# mega-shield2.net
KiCad netlist of a schematic drawn in EAGLE
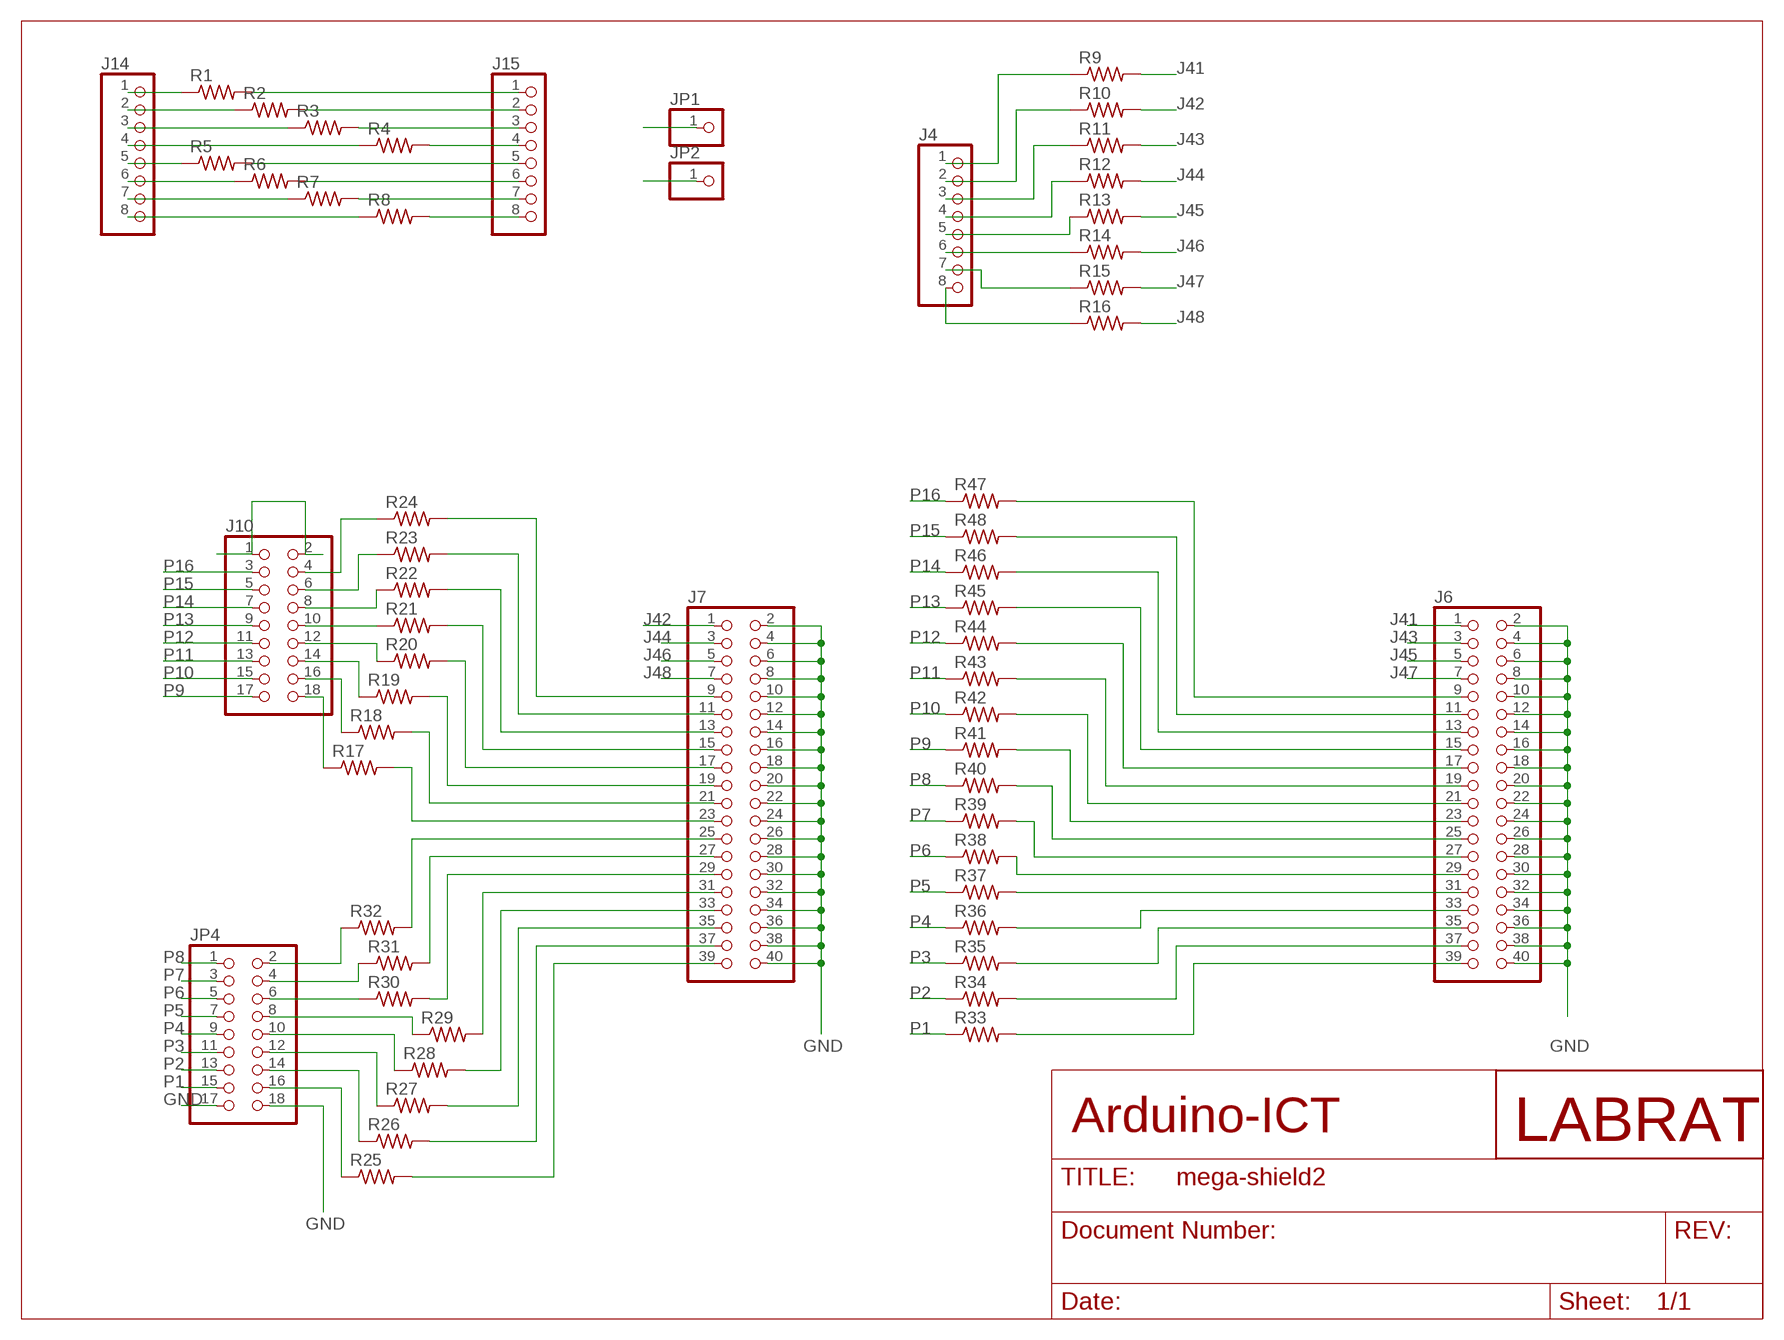
[diagram p0: schematic, sheet 1]

(export (version "E")
  (design (tool "Eeschema 10.0.6"))
  (components
    (comp (ref "J4")
      (value "PINHD-1X8BIG")
      (footprint "eagle-import:1X08-BIG")
      (libsource (lib "eagle-import") (part "PINHD-1X8BIG"))
    )
    (comp (ref "J6")
      (value "PINHD-2X20")
      (footprint "eagle-import:2X20")
      (libsource (lib "eagle-import") (part "PINHD-2X20"))
    )
    (comp (ref "J7")
      (value "PINHD-2X20")
      (footprint "eagle-import:2X20")
      (libsource (lib "eagle-import") (part "PINHD-2X20"))
    )
    (comp (ref "J10")
      (value "PINHD-2X9-BIG")
      (footprint "eagle-import:2X09-BIG")
      (libsource (lib "eagle-import") (part "PINHD-2X9-BIG"))
    )
    (comp (ref "J14")
      (value "PINHD-1X8BIG")
      (footprint "eagle-import:1X08-BIG")
      (libsource (lib "eagle-import") (part "PINHD-1X8BIG"))
    )
    (comp (ref "J15")
      (value "PINHD-1X8BIG")
      (footprint "eagle-import:1X08-BIG")
      (libsource (lib "eagle-import") (part "PINHD-1X8BIG"))
    )
    (comp (ref "JP1")
      (value "PINHD-1X1")
      (footprint "eagle-import:1X01")
      (libsource (lib "eagle-import") (part "PINHD-1X1"))
    )
    (comp (ref "JP2")
      (value "PINHD-1X1")
      (footprint "eagle-import:1X01")
      (libsource (lib "eagle-import") (part "PINHD-1X1"))
    )
    (comp (ref "JP4")
      (value "PINHD-2X9-BIG")
      (footprint "eagle-import:2X09-BIG")
      (libsource (lib "eagle-import") (part "PINHD-2X9-BIG"))
    )
    (comp (ref "R1")
      (value "R-US_0204/5")
      (footprint "eagle-import:0204_5")
      (libsource (lib "eagle-import") (part "R-US_0204/5"))
    )
    (comp (ref "R2")
      (value "R-US_0204/5")
      (footprint "eagle-import:0204_5")
      (libsource (lib "eagle-import") (part "R-US_0204/5"))
    )
    (comp (ref "R3")
      (value "R-US_0204/5")
      (footprint "eagle-import:0204_5")
      (libsource (lib "eagle-import") (part "R-US_0204/5"))
    )
    (comp (ref "R4")
      (value "R-US_0204/5")
      (footprint "eagle-import:0204_5")
      (libsource (lib "eagle-import") (part "R-US_0204/5"))
    )
    (comp (ref "R5")
      (value "R-US_0204/5")
      (footprint "eagle-import:0204_5")
      (libsource (lib "eagle-import") (part "R-US_0204/5"))
    )
    (comp (ref "R6")
      (value "R-US_0204/5")
      (footprint "eagle-import:0204_5")
      (libsource (lib "eagle-import") (part "R-US_0204/5"))
    )
    (comp (ref "R7")
      (value "R-US_0204/5")
      (footprint "eagle-import:0204_5")
      (libsource (lib "eagle-import") (part "R-US_0204/5"))
    )
    (comp (ref "R8")
      (value "R-US_0204/5")
      (footprint "eagle-import:0204_5")
      (libsource (lib "eagle-import") (part "R-US_0204/5"))
    )
    (comp (ref "R9")
      (value "R-US_0204/5")
      (footprint "eagle-import:0204_5")
      (libsource (lib "eagle-import") (part "R-US_0204/5"))
    )
    (comp (ref "R10")
      (value "R-US_0204/5")
      (footprint "eagle-import:0204_5")
      (libsource (lib "eagle-import") (part "R-US_0204/5"))
    )
    (comp (ref "R11")
      (value "R-US_0204/5")
      (footprint "eagle-import:0204_5")
      (libsource (lib "eagle-import") (part "R-US_0204/5"))
    )
    (comp (ref "R12")
      (value "R-US_0204/5")
      (footprint "eagle-import:0204_5")
      (libsource (lib "eagle-import") (part "R-US_0204/5"))
    )
    (comp (ref "R13")
      (value "R-US_0204/5")
      (footprint "eagle-import:0204_5")
      (libsource (lib "eagle-import") (part "R-US_0204/5"))
    )
    (comp (ref "R14")
      (value "R-US_0204/5")
      (footprint "eagle-import:0204_5")
      (libsource (lib "eagle-import") (part "R-US_0204/5"))
    )
    (comp (ref "R15")
      (value "R-US_0204/5")
      (footprint "eagle-import:0204_5")
      (libsource (lib "eagle-import") (part "R-US_0204/5"))
    )
    (comp (ref "R16")
      (value "R-US_0204/5")
      (footprint "eagle-import:0204_5")
      (libsource (lib "eagle-import") (part "R-US_0204/5"))
    )
    (comp (ref "R17")
      (value "R-US_0204/5")
      (footprint "eagle-import:0204_5")
      (libsource (lib "eagle-import") (part "R-US_0204/5"))
    )
    (comp (ref "R18")
      (value "R-US_0204/5")
      (footprint "eagle-import:0204_5")
      (libsource (lib "eagle-import") (part "R-US_0204/5"))
    )
    (comp (ref "R19")
      (value "R-US_0204/5")
      (footprint "eagle-import:0204_5")
      (libsource (lib "eagle-import") (part "R-US_0204/5"))
    )
    (comp (ref "R20")
      (value "R-US_0204/5")
      (footprint "eagle-import:0204_5")
      (libsource (lib "eagle-import") (part "R-US_0204/5"))
    )
    (comp (ref "R21")
      (value "R-US_0204/5")
      (footprint "eagle-import:0204_5")
      (libsource (lib "eagle-import") (part "R-US_0204/5"))
    )
    (comp (ref "R22")
      (value "R-US_0204/5")
      (footprint "eagle-import:0204_5")
      (libsource (lib "eagle-import") (part "R-US_0204/5"))
    )
    (comp (ref "R23")
      (value "R-US_0204/5")
      (footprint "eagle-import:0204_5")
      (libsource (lib "eagle-import") (part "R-US_0204/5"))
    )
    (comp (ref "R24")
      (value "R-US_0204/5")
      (footprint "eagle-import:0204_5")
      (libsource (lib "eagle-import") (part "R-US_0204/5"))
    )
    (comp (ref "R25")
      (value "R-US_0204/5")
      (footprint "eagle-import:0204_5")
      (libsource (lib "eagle-import") (part "R-US_0204/5"))
    )
    (comp (ref "R26")
      (value "R-US_0204/5")
      (footprint "eagle-import:0204_5")
      (libsource (lib "eagle-import") (part "R-US_0204/5"))
    )
    (comp (ref "R27")
      (value "R-US_0204/5")
      (footprint "eagle-import:0204_5")
      (libsource (lib "eagle-import") (part "R-US_0204/5"))
    )
    (comp (ref "R28")
      (value "R-US_0204/5")
      (footprint "eagle-import:0204_5")
      (libsource (lib "eagle-import") (part "R-US_0204/5"))
    )
    (comp (ref "R29")
      (value "R-US_0204/5")
      (footprint "eagle-import:0204_5")
      (libsource (lib "eagle-import") (part "R-US_0204/5"))
    )
    (comp (ref "R30")
      (value "R-US_0204/5")
      (footprint "eagle-import:0204_5")
      (libsource (lib "eagle-import") (part "R-US_0204/5"))
    )
    (comp (ref "R31")
      (value "R-US_0204/5")
      (footprint "eagle-import:0204_5")
      (libsource (lib "eagle-import") (part "R-US_0204/5"))
    )
    (comp (ref "R32")
      (value "R-US_0204/5")
      (footprint "eagle-import:0204_5")
      (libsource (lib "eagle-import") (part "R-US_0204/5"))
    )
    (comp (ref "R33")
      (value "R-US_0204/5")
      (footprint "eagle-import:0204_5")
      (libsource (lib "eagle-import") (part "R-US_0204/5"))
    )
    (comp (ref "R34")
      (value "R-US_0204/5")
      (footprint "eagle-import:0204_5")
      (libsource (lib "eagle-import") (part "R-US_0204/5"))
    )
    (comp (ref "R35")
      (value "R-US_0204/5")
      (footprint "eagle-import:0204_5")
      (libsource (lib "eagle-import") (part "R-US_0204/5"))
    )
    (comp (ref "R36")
      (value "R-US_0204/5")
      (footprint "eagle-import:0204_5")
      (libsource (lib "eagle-import") (part "R-US_0204/5"))
    )
    (comp (ref "R37")
      (value "R-US_0204/5")
      (footprint "eagle-import:0204_5")
      (libsource (lib "eagle-import") (part "R-US_0204/5"))
    )
    (comp (ref "R38")
      (value "R-US_0204/5")
      (footprint "eagle-import:0204_5")
      (libsource (lib "eagle-import") (part "R-US_0204/5"))
    )
    (comp (ref "R39")
      (value "R-US_0204/5")
      (footprint "eagle-import:0204_5")
      (libsource (lib "eagle-import") (part "R-US_0204/5"))
    )
    (comp (ref "R40")
      (value "R-US_0204/5")
      (footprint "eagle-import:0204_5")
      (libsource (lib "eagle-import") (part "R-US_0204/5"))
    )
    (comp (ref "R41")
      (value "R-US_0204/5")
      (footprint "eagle-import:0204_5")
      (libsource (lib "eagle-import") (part "R-US_0204/5"))
    )
    (comp (ref "R42")
      (value "R-US_0204/5")
      (footprint "eagle-import:0204_5")
      (libsource (lib "eagle-import") (part "R-US_0204/5"))
    )
    (comp (ref "R43")
      (value "R-US_0204/5")
      (footprint "eagle-import:0204_5")
      (libsource (lib "eagle-import") (part "R-US_0204/5"))
    )
    (comp (ref "R44")
      (value "R-US_0204/5")
      (footprint "eagle-import:0204_5")
      (libsource (lib "eagle-import") (part "R-US_0204/5"))
    )
    (comp (ref "R45")
      (value "R-US_0204/5")
      (footprint "eagle-import:0204_5")
      (libsource (lib "eagle-import") (part "R-US_0204/5"))
    )
    (comp (ref "R46")
      (value "R-US_0204/5")
      (footprint "eagle-import:0204_5")
      (libsource (lib "eagle-import") (part "R-US_0204/5"))
    )
    (comp (ref "R47")
      (value "R-US_0204/5")
      (footprint "eagle-import:0204_5")
      (libsource (lib "eagle-import") (part "R-US_0204/5"))
    )
    (comp (ref "R48")
      (value "R-US_0204/5")
      (footprint "eagle-import:0204_5")
      (libsource (lib "eagle-import") (part "R-US_0204/5"))
    )
    (comp (ref "U$1")
      (value "LOGOLABRAT")
      (footprint "eagle-import:LOGO")
      (libsource (lib "eagle-import") (part "LOGOLABRAT"))
    )
  )
  (nets
    (net (code "1") (name "/GND") (class "Default")
      (node (ref "J6") (pin "10") (pinfunction "10_10") (pintype "passive"))
      (node (ref "J6") (pin "12") (pinfunction "12_12") (pintype "passive"))
      (node (ref "J6") (pin "14") (pinfunction "14_14") (pintype "passive"))
      (node (ref "J6") (pin "16") (pinfunction "16_16") (pintype "passive"))
      (node (ref "J6") (pin "18") (pinfunction "18_18") (pintype "passive"))
      (node (ref "J6") (pin "2") (pinfunction "2_2") (pintype "passive"))
      (node (ref "J6") (pin "20") (pinfunction "20_20") (pintype "passive"))
      (node (ref "J6") (pin "22") (pinfunction "22_22") (pintype "passive"))
      (node (ref "J6") (pin "24") (pinfunction "24_24") (pintype "passive"))
      (node (ref "J6") (pin "26") (pinfunction "26_26") (pintype "passive"))
      (node (ref "J6") (pin "28") (pinfunction "28_28") (pintype "passive"))
      (node (ref "J6") (pin "30") (pinfunction "30_30") (pintype "passive"))
      (node (ref "J6") (pin "32") (pinfunction "32_32") (pintype "passive"))
      (node (ref "J6") (pin "34") (pinfunction "34_34") (pintype "passive"))
      (node (ref "J6") (pin "36") (pinfunction "36_36") (pintype "passive"))
      (node (ref "J6") (pin "38") (pinfunction "38_38") (pintype "passive"))
      (node (ref "J6") (pin "4") (pinfunction "4_4") (pintype "passive"))
      (node (ref "J6") (pin "40") (pinfunction "40_40") (pintype "passive"))
      (node (ref "J6") (pin "6") (pinfunction "6_6") (pintype "passive"))
      (node (ref "J6") (pin "8") (pinfunction "8_8") (pintype "passive"))
      (node (ref "J7") (pin "10") (pinfunction "10_10") (pintype "passive"))
      (node (ref "J7") (pin "12") (pinfunction "12_12") (pintype "passive"))
      (node (ref "J7") (pin "14") (pinfunction "14_14") (pintype "passive"))
      (node (ref "J7") (pin "16") (pinfunction "16_16") (pintype "passive"))
      (node (ref "J7") (pin "18") (pinfunction "18_18") (pintype "passive"))
      (node (ref "J7") (pin "2") (pinfunction "2_2") (pintype "passive"))
      (node (ref "J7") (pin "20") (pinfunction "20_20") (pintype "passive"))
      (node (ref "J7") (pin "22") (pinfunction "22_22") (pintype "passive"))
      (node (ref "J7") (pin "24") (pinfunction "24_24") (pintype "passive"))
      (node (ref "J7") (pin "26") (pinfunction "26_26") (pintype "passive"))
      (node (ref "J7") (pin "28") (pinfunction "28_28") (pintype "passive"))
      (node (ref "J7") (pin "30") (pinfunction "30_30") (pintype "passive"))
      (node (ref "J7") (pin "32") (pinfunction "32_32") (pintype "passive"))
      (node (ref "J7") (pin "34") (pinfunction "34_34") (pintype "passive"))
      (node (ref "J7") (pin "36") (pinfunction "36_36") (pintype "passive"))
      (node (ref "J7") (pin "38") (pinfunction "38_38") (pintype "passive"))
      (node (ref "J7") (pin "4") (pinfunction "4_4") (pintype "passive"))
      (node (ref "J7") (pin "40") (pinfunction "40_40") (pintype "passive"))
      (node (ref "J7") (pin "6") (pinfunction "6_6") (pintype "passive"))
      (node (ref "J7") (pin "8") (pinfunction "8_8") (pintype "passive"))
      (node (ref "JP1") (pin "1") (pinfunction "1_1") (pintype "passive"))
      (node (ref "JP2") (pin "1") (pinfunction "1_1") (pintype "passive"))
      (node (ref "JP4") (pin "17") (pinfunction "17_17") (pintype "passive"))
      (node (ref "JP4") (pin "18") (pinfunction "18_18") (pintype "passive"))
    )
    (net (code "2") (name "/J41") (class "Default")
      (node (ref "J6") (pin "1") (pinfunction "1_1") (pintype "passive"))
      (node (ref "R9") (pin "2") (pinfunction "2_2") (pintype "passive"))
    )
    (net (code "3") (name "/J42") (class "Default")
      (node (ref "J7") (pin "1") (pinfunction "1_1") (pintype "passive"))
      (node (ref "R10") (pin "2") (pinfunction "2_2") (pintype "passive"))
    )
    (net (code "4") (name "/J43") (class "Default")
      (node (ref "J6") (pin "3") (pinfunction "3_3") (pintype "passive"))
      (node (ref "R11") (pin "2") (pinfunction "2_2") (pintype "passive"))
    )
    (net (code "5") (name "/J44") (class "Default")
      (node (ref "J7") (pin "3") (pinfunction "3_3") (pintype "passive"))
      (node (ref "R12") (pin "2") (pinfunction "2_2") (pintype "passive"))
    )
    (net (code "6") (name "/J45") (class "Default")
      (node (ref "J6") (pin "5") (pinfunction "5_5") (pintype "passive"))
      (node (ref "R13") (pin "2") (pinfunction "2_2") (pintype "passive"))
    )
    (net (code "7") (name "/J46") (class "Default")
      (node (ref "J7") (pin "5") (pinfunction "5_5") (pintype "passive"))
      (node (ref "R14") (pin "2") (pinfunction "2_2") (pintype "passive"))
    )
    (net (code "8") (name "/J47") (class "Default")
      (node (ref "J6") (pin "7") (pinfunction "7_7") (pintype "passive"))
      (node (ref "R15") (pin "2") (pinfunction "2_2") (pintype "passive"))
    )
    (net (code "9") (name "/J48") (class "Default")
      (node (ref "J7") (pin "7") (pinfunction "7_7") (pintype "passive"))
      (node (ref "R16") (pin "2") (pinfunction "2_2") (pintype "passive"))
    )
    (net (code "10") (name "/P1") (class "Default")
      (node (ref "JP4") (pin "15") (pinfunction "15_15") (pintype "passive"))
      (node (ref "R33") (pin "1") (pinfunction "1_1") (pintype "passive"))
    )
    (net (code "11") (name "/P2") (class "Default")
      (node (ref "JP4") (pin "13") (pinfunction "13_13") (pintype "passive"))
      (node (ref "R34") (pin "1") (pinfunction "1_1") (pintype "passive"))
    )
    (net (code "12") (name "/P3") (class "Default")
      (node (ref "JP4") (pin "11") (pinfunction "11_11") (pintype "passive"))
      (node (ref "R35") (pin "1") (pinfunction "1_1") (pintype "passive"))
    )
    (net (code "13") (name "/P4") (class "Default")
      (node (ref "JP4") (pin "9") (pinfunction "9_9") (pintype "passive"))
      (node (ref "R36") (pin "1") (pinfunction "1_1") (pintype "passive"))
    )
    (net (code "14") (name "/P5") (class "Default")
      (node (ref "JP4") (pin "7") (pinfunction "7_7") (pintype "passive"))
      (node (ref "R37") (pin "1") (pinfunction "1_1") (pintype "passive"))
    )
    (net (code "15") (name "/P6") (class "Default")
      (node (ref "JP4") (pin "5") (pinfunction "5_5") (pintype "passive"))
      (node (ref "R38") (pin "1") (pinfunction "1_1") (pintype "passive"))
    )
    (net (code "16") (name "/P7") (class "Default")
      (node (ref "JP4") (pin "3") (pinfunction "3_3") (pintype "passive"))
      (node (ref "R39") (pin "1") (pinfunction "1_1") (pintype "passive"))
    )
    (net (code "17") (name "/P8") (class "Default")
      (node (ref "JP4") (pin "1") (pinfunction "1_1") (pintype "passive"))
      (node (ref "R40") (pin "1") (pinfunction "1_1") (pintype "passive"))
    )
    (net (code "18") (name "/P9") (class "Default")
      (node (ref "J10") (pin "17") (pinfunction "17_17") (pintype "passive"))
      (node (ref "R41") (pin "1") (pinfunction "1_1") (pintype "passive"))
    )
    (net (code "19") (name "/P10") (class "Default")
      (node (ref "J10") (pin "15") (pinfunction "15_15") (pintype "passive"))
      (node (ref "R42") (pin "1") (pinfunction "1_1") (pintype "passive"))
    )
    (net (code "20") (name "/P11") (class "Default")
      (node (ref "J10") (pin "13") (pinfunction "13_13") (pintype "passive"))
      (node (ref "R43") (pin "1") (pinfunction "1_1") (pintype "passive"))
    )
    (net (code "21") (name "/P12") (class "Default")
      (node (ref "J10") (pin "11") (pinfunction "11_11") (pintype "passive"))
      (node (ref "R44") (pin "1") (pinfunction "1_1") (pintype "passive"))
    )
    (net (code "22") (name "/P13") (class "Default")
      (node (ref "J10") (pin "9") (pinfunction "9_9") (pintype "passive"))
      (node (ref "R45") (pin "1") (pinfunction "1_1") (pintype "passive"))
    )
    (net (code "23") (name "/P14") (class "Default")
      (node (ref "J10") (pin "7") (pinfunction "7_7") (pintype "passive"))
      (node (ref "R46") (pin "1") (pinfunction "1_1") (pintype "passive"))
    )
    (net (code "24") (name "/P15") (class "Default")
      (node (ref "J10") (pin "5") (pinfunction "5_5") (pintype "passive"))
      (node (ref "R48") (pin "1") (pinfunction "1_1") (pintype "passive"))
    )
    (net (code "25") (name "/P16") (class "Default")
      (node (ref "J10") (pin "3") (pinfunction "3_3") (pintype "passive"))
      (node (ref "R47") (pin "1") (pinfunction "1_1") (pintype "passive"))
    )
    (net (code "26") (name "Net-(J4-Pad1)") (class "Default")
      (node (ref "J4") (pin "1") (pinfunction "1_1") (pintype "passive"))
      (node (ref "R9") (pin "1") (pinfunction "1_1") (pintype "passive"))
    )
    (net (code "27") (name "Net-(J4-Pad2)") (class "Default")
      (node (ref "J4") (pin "2") (pinfunction "2_2") (pintype "passive"))
      (node (ref "R10") (pin "1") (pinfunction "1_1") (pintype "passive"))
    )
    (net (code "28") (name "Net-(J4-Pad3)") (class "Default")
      (node (ref "J4") (pin "3") (pinfunction "3_3") (pintype "passive"))
      (node (ref "R11") (pin "1") (pinfunction "1_1") (pintype "passive"))
    )
    (net (code "29") (name "Net-(J4-Pad4)") (class "Default")
      (node (ref "J4") (pin "4") (pinfunction "4_4") (pintype "passive"))
      (node (ref "R12") (pin "1") (pinfunction "1_1") (pintype "passive"))
    )
    (net (code "30") (name "Net-(J4-Pad5)") (class "Default")
      (node (ref "J4") (pin "5") (pinfunction "5_5") (pintype "passive"))
      (node (ref "R13") (pin "1") (pinfunction "1_1") (pintype "passive"))
    )
    (net (code "31") (name "Net-(J4-Pad6)") (class "Default")
      (node (ref "J4") (pin "6") (pinfunction "6_6") (pintype "passive"))
      (node (ref "R14") (pin "1") (pinfunction "1_1") (pintype "passive"))
    )
    (net (code "32") (name "Net-(J4-Pad7)") (class "Default")
      (node (ref "J4") (pin "7") (pinfunction "7_7") (pintype "passive"))
      (node (ref "R15") (pin "1") (pinfunction "1_1") (pintype "passive"))
    )
    (net (code "33") (name "Net-(J4-Pad8)") (class "Default")
      (node (ref "J4") (pin "8") (pinfunction "8_8") (pintype "passive"))
      (node (ref "R16") (pin "1") (pinfunction "1_1") (pintype "passive"))
    )
    (net (code "34") (name "Net-(J6-Pad9)") (class "Default")
      (node (ref "J6") (pin "9") (pinfunction "9_9") (pintype "passive"))
      (node (ref "R47") (pin "2") (pinfunction "2_2") (pintype "passive"))
    )
    (net (code "35") (name "Net-(J6-Pad11)") (class "Default")
      (node (ref "J6") (pin "11") (pinfunction "11_11") (pintype "passive"))
      (node (ref "R48") (pin "2") (pinfunction "2_2") (pintype "passive"))
    )
    (net (code "36") (name "Net-(J6-Pad13)") (class "Default")
      (node (ref "J6") (pin "13") (pinfunction "13_13") (pintype "passive"))
      (node (ref "R46") (pin "2") (pinfunction "2_2") (pintype "passive"))
    )
    (net (code "37") (name "Net-(J6-Pad15)") (class "Default")
      (node (ref "J6") (pin "15") (pinfunction "15_15") (pintype "passive"))
      (node (ref "R45") (pin "2") (pinfunction "2_2") (pintype "passive"))
    )
    (net (code "38") (name "Net-(J6-Pad17)") (class "Default")
      (node (ref "J6") (pin "17") (pinfunction "17_17") (pintype "passive"))
      (node (ref "R44") (pin "2") (pinfunction "2_2") (pintype "passive"))
    )
    (net (code "39") (name "Net-(J6-Pad19)") (class "Default")
      (node (ref "J6") (pin "19") (pinfunction "19_19") (pintype "passive"))
      (node (ref "R43") (pin "2") (pinfunction "2_2") (pintype "passive"))
    )
    (net (code "40") (name "Net-(J6-Pad21)") (class "Default")
      (node (ref "J6") (pin "21") (pinfunction "21_21") (pintype "passive"))
      (node (ref "R42") (pin "2") (pinfunction "2_2") (pintype "passive"))
    )
    (net (code "41") (name "Net-(J6-Pad23)") (class "Default")
      (node (ref "J6") (pin "23") (pinfunction "23_23") (pintype "passive"))
      (node (ref "R41") (pin "2") (pinfunction "2_2") (pintype "passive"))
    )
    (net (code "42") (name "Net-(J6-Pad25)") (class "Default")
      (node (ref "J6") (pin "25") (pinfunction "25_25") (pintype "passive"))
      (node (ref "R40") (pin "2") (pinfunction "2_2") (pintype "passive"))
    )
    (net (code "43") (name "Net-(J6-Pad27)") (class "Default")
      (node (ref "J6") (pin "27") (pinfunction "27_27") (pintype "passive"))
      (node (ref "R39") (pin "2") (pinfunction "2_2") (pintype "passive"))
    )
    (net (code "44") (name "Net-(J6-Pad29)") (class "Default")
      (node (ref "J6") (pin "29") (pinfunction "29_29") (pintype "passive"))
      (node (ref "R38") (pin "2") (pinfunction "2_2") (pintype "passive"))
    )
    (net (code "45") (name "Net-(J6-Pad31)") (class "Default")
      (node (ref "J6") (pin "31") (pinfunction "31_31") (pintype "passive"))
      (node (ref "R37") (pin "2") (pinfunction "2_2") (pintype "passive"))
    )
    (net (code "46") (name "Net-(J6-Pad33)") (class "Default")
      (node (ref "J6") (pin "33") (pinfunction "33_33") (pintype "passive"))
      (node (ref "R36") (pin "2") (pinfunction "2_2") (pintype "passive"))
    )
    (net (code "47") (name "Net-(J6-Pad35)") (class "Default")
      (node (ref "J6") (pin "35") (pinfunction "35_35") (pintype "passive"))
      (node (ref "R35") (pin "2") (pinfunction "2_2") (pintype "passive"))
    )
    (net (code "48") (name "Net-(J6-Pad37)") (class "Default")
      (node (ref "J6") (pin "37") (pinfunction "37_37") (pintype "passive"))
      (node (ref "R34") (pin "2") (pinfunction "2_2") (pintype "passive"))
    )
    (net (code "49") (name "Net-(J6-Pad39)") (class "Default")
      (node (ref "J6") (pin "39") (pinfunction "39_39") (pintype "passive"))
      (node (ref "R33") (pin "2") (pinfunction "2_2") (pintype "passive"))
    )
    (net (code "50") (name "Net-(J7-Pad9)") (class "Default")
      (node (ref "J7") (pin "9") (pinfunction "9_9") (pintype "passive"))
      (node (ref "R24") (pin "2") (pinfunction "2_2") (pintype "passive"))
    )
    (net (code "51") (name "Net-(J7-Pad11)") (class "Default")
      (node (ref "J7") (pin "11") (pinfunction "11_11") (pintype "passive"))
      (node (ref "R23") (pin "2") (pinfunction "2_2") (pintype "passive"))
    )
    (net (code "52") (name "Net-(J7-Pad13)") (class "Default")
      (node (ref "J7") (pin "13") (pinfunction "13_13") (pintype "passive"))
      (node (ref "R22") (pin "2") (pinfunction "2_2") (pintype "passive"))
    )
    (net (code "53") (name "Net-(J7-Pad15)") (class "Default")
      (node (ref "J7") (pin "15") (pinfunction "15_15") (pintype "passive"))
      (node (ref "R21") (pin "2") (pinfunction "2_2") (pintype "passive"))
    )
    (net (code "54") (name "Net-(J7-Pad17)") (class "Default")
      (node (ref "J7") (pin "17") (pinfunction "17_17") (pintype "passive"))
      (node (ref "R20") (pin "2") (pinfunction "2_2") (pintype "passive"))
    )
    (net (code "55") (name "Net-(J7-Pad19)") (class "Default")
      (node (ref "J7") (pin "19") (pinfunction "19_19") (pintype "passive"))
      (node (ref "R19") (pin "2") (pinfunction "2_2") (pintype "passive"))
    )
    (net (code "56") (name "Net-(J7-Pad21)") (class "Default")
      (node (ref "J7") (pin "21") (pinfunction "21_21") (pintype "passive"))
      (node (ref "R18") (pin "2") (pinfunction "2_2") (pintype "passive"))
    )
    (net (code "57") (name "Net-(J7-Pad23)") (class "Default")
      (node (ref "J7") (pin "23") (pinfunction "23_23") (pintype "passive"))
      (node (ref "R17") (pin "2") (pinfunction "2_2") (pintype "passive"))
    )
    (net (code "58") (name "Net-(J7-Pad25)") (class "Default")
      (node (ref "J7") (pin "25") (pinfunction "25_25") (pintype "passive"))
      (node (ref "R32") (pin "2") (pinfunction "2_2") (pintype "passive"))
    )
    (net (code "59") (name "Net-(J7-Pad27)") (class "Default")
      (node (ref "J7") (pin "27") (pinfunction "27_27") (pintype "passive"))
      (node (ref "R31") (pin "2") (pinfunction "2_2") (pintype "passive"))
    )
    (net (code "60") (name "Net-(J7-Pad29)") (class "Default")
      (node (ref "J7") (pin "29") (pinfunction "29_29") (pintype "passive"))
      (node (ref "R30") (pin "2") (pinfunction "2_2") (pintype "passive"))
    )
    (net (code "61") (name "Net-(J7-Pad31)") (class "Default")
      (node (ref "J7") (pin "31") (pinfunction "31_31") (pintype "passive"))
      (node (ref "R29") (pin "2") (pinfunction "2_2") (pintype "passive"))
    )
    (net (code "62") (name "Net-(J7-Pad33)") (class "Default")
      (node (ref "J7") (pin "33") (pinfunction "33_33") (pintype "passive"))
      (node (ref "R28") (pin "2") (pinfunction "2_2") (pintype "passive"))
    )
    (net (code "63") (name "Net-(J7-Pad35)") (class "Default")
      (node (ref "J7") (pin "35") (pinfunction "35_35") (pintype "passive"))
      (node (ref "R27") (pin "2") (pinfunction "2_2") (pintype "passive"))
    )
    (net (code "64") (name "Net-(J7-Pad37)") (class "Default")
      (node (ref "J7") (pin "37") (pinfunction "37_37") (pintype "passive"))
      (node (ref "R26") (pin "2") (pinfunction "2_2") (pintype "passive"))
    )
    (net (code "65") (name "Net-(J7-Pad39)") (class "Default")
      (node (ref "J7") (pin "39") (pinfunction "39_39") (pintype "passive"))
      (node (ref "R25") (pin "2") (pinfunction "2_2") (pintype "passive"))
    )
    (net (code "66") (name "Net-(J10-Pad1)") (class "Default")
      (node (ref "J10") (pin "1") (pinfunction "1_1") (pintype "passive"))
      (node (ref "J10") (pin "2") (pinfunction "2_2") (pintype "passive"))
    )
    (net (code "67") (name "Net-(J10-Pad4)") (class "Default")
      (node (ref "J10") (pin "4") (pinfunction "4_4") (pintype "passive"))
      (node (ref "R24") (pin "1") (pinfunction "1_1") (pintype "passive"))
    )
    (net (code "68") (name "Net-(J10-Pad6)") (class "Default")
      (node (ref "J10") (pin "6") (pinfunction "6_6") (pintype "passive"))
      (node (ref "R23") (pin "1") (pinfunction "1_1") (pintype "passive"))
    )
    (net (code "69") (name "Net-(J10-Pad8)") (class "Default")
      (node (ref "J10") (pin "8") (pinfunction "8_8") (pintype "passive"))
      (node (ref "R22") (pin "1") (pinfunction "1_1") (pintype "passive"))
    )
    (net (code "70") (name "Net-(J10-Pad10)") (class "Default")
      (node (ref "J10") (pin "10") (pinfunction "10_10") (pintype "passive"))
      (node (ref "R21") (pin "1") (pinfunction "1_1") (pintype "passive"))
    )
    (net (code "71") (name "Net-(J10-Pad12)") (class "Default")
      (node (ref "J10") (pin "12") (pinfunction "12_12") (pintype "passive"))
      (node (ref "R20") (pin "1") (pinfunction "1_1") (pintype "passive"))
    )
    (net (code "72") (name "Net-(J10-Pad14)") (class "Default")
      (node (ref "J10") (pin "14") (pinfunction "14_14") (pintype "passive"))
      (node (ref "R19") (pin "1") (pinfunction "1_1") (pintype "passive"))
    )
    (net (code "73") (name "Net-(J10-Pad16)") (class "Default")
      (node (ref "J10") (pin "16") (pinfunction "16_16") (pintype "passive"))
      (node (ref "R18") (pin "1") (pinfunction "1_1") (pintype "passive"))
    )
    (net (code "74") (name "Net-(J10-Pad18)") (class "Default")
      (node (ref "J10") (pin "18") (pinfunction "18_18") (pintype "passive"))
      (node (ref "R17") (pin "1") (pinfunction "1_1") (pintype "passive"))
    )
    (net (code "75") (name "Net-(J14-Pad1)") (class "Default")
      (node (ref "J14") (pin "1") (pinfunction "1_1") (pintype "passive"))
      (node (ref "R1") (pin "1") (pinfunction "1_1") (pintype "passive"))
    )
    (net (code "76") (name "Net-(J14-Pad2)") (class "Default")
      (node (ref "J14") (pin "2") (pinfunction "2_2") (pintype "passive"))
      (node (ref "R2") (pin "1") (pinfunction "1_1") (pintype "passive"))
    )
    (net (code "77") (name "Net-(J14-Pad3)") (class "Default")
      (node (ref "J14") (pin "3") (pinfunction "3_3") (pintype "passive"))
      (node (ref "R3") (pin "1") (pinfunction "1_1") (pintype "passive"))
    )
    (net (code "78") (name "Net-(J14-Pad4)") (class "Default")
      (node (ref "J14") (pin "4") (pinfunction "4_4") (pintype "passive"))
      (node (ref "R4") (pin "1") (pinfunction "1_1") (pintype "passive"))
    )
    (net (code "79") (name "Net-(J14-Pad5)") (class "Default")
      (node (ref "J14") (pin "5") (pinfunction "5_5") (pintype "passive"))
      (node (ref "R5") (pin "1") (pinfunction "1_1") (pintype "passive"))
    )
    (net (code "80") (name "Net-(J14-Pad6)") (class "Default")
      (node (ref "J14") (pin "6") (pinfunction "6_6") (pintype "passive"))
      (node (ref "R6") (pin "1") (pinfunction "1_1") (pintype "passive"))
    )
    (net (code "81") (name "Net-(J14-Pad7)") (class "Default")
      (node (ref "J14") (pin "7") (pinfunction "7_7") (pintype "passive"))
      (node (ref "R7") (pin "1") (pinfunction "1_1") (pintype "passive"))
    )
    (net (code "82") (name "Net-(J14-Pad8)") (class "Default")
      (node (ref "J14") (pin "8") (pinfunction "8_8") (pintype "passive"))
      (node (ref "R8") (pin "1") (pinfunction "1_1") (pintype "passive"))
    )
    (net (code "83") (name "Net-(J15-Pad1)") (class "Default")
      (node (ref "J15") (pin "1") (pinfunction "1_1") (pintype "passive"))
      (node (ref "R1") (pin "2") (pinfunction "2_2") (pintype "passive"))
    )
    (net (code "84") (name "Net-(J15-Pad2)") (class "Default")
      (node (ref "J15") (pin "2") (pinfunction "2_2") (pintype "passive"))
      (node (ref "R2") (pin "2") (pinfunction "2_2") (pintype "passive"))
    )
    (net (code "85") (name "Net-(J15-Pad3)") (class "Default")
      (node (ref "J15") (pin "3") (pinfunction "3_3") (pintype "passive"))
      (node (ref "R3") (pin "2") (pinfunction "2_2") (pintype "passive"))
    )
    (net (code "86") (name "Net-(J15-Pad4)") (class "Default")
      (node (ref "J15") (pin "4") (pinfunction "4_4") (pintype "passive"))
      (node (ref "R4") (pin "2") (pinfunction "2_2") (pintype "passive"))
    )
    (net (code "87") (name "Net-(J15-Pad5)") (class "Default")
      (node (ref "J15") (pin "5") (pinfunction "5_5") (pintype "passive"))
      (node (ref "R5") (pin "2") (pinfunction "2_2") (pintype "passive"))
    )
    (net (code "88") (name "Net-(J15-Pad6)") (class "Default")
      (node (ref "J15") (pin "6") (pinfunction "6_6") (pintype "passive"))
      (node (ref "R6") (pin "2") (pinfunction "2_2") (pintype "passive"))
    )
    (net (code "89") (name "Net-(J15-Pad7)") (class "Default")
      (node (ref "J15") (pin "7") (pinfunction "7_7") (pintype "passive"))
      (node (ref "R7") (pin "2") (pinfunction "2_2") (pintype "passive"))
    )
    (net (code "90") (name "Net-(J15-Pad8)") (class "Default")
      (node (ref "J15") (pin "8") (pinfunction "8_8") (pintype "passive"))
      (node (ref "R8") (pin "2") (pinfunction "2_2") (pintype "passive"))
    )
    (net (code "91") (name "Net-(JP4-Pad2)") (class "Default")
      (node (ref "JP4") (pin "2") (pinfunction "2_2") (pintype "passive"))
      (node (ref "R32") (pin "1") (pinfunction "1_1") (pintype "passive"))
    )
    (net (code "92") (name "Net-(JP4-Pad4)") (class "Default")
      (node (ref "JP4") (pin "4") (pinfunction "4_4") (pintype "passive"))
      (node (ref "R31") (pin "1") (pinfunction "1_1") (pintype "passive"))
    )
    (net (code "93") (name "Net-(JP4-Pad6)") (class "Default")
      (node (ref "JP4") (pin "6") (pinfunction "6_6") (pintype "passive"))
      (node (ref "R30") (pin "1") (pinfunction "1_1") (pintype "passive"))
    )
    (net (code "94") (name "Net-(JP4-Pad8)") (class "Default")
      (node (ref "JP4") (pin "8") (pinfunction "8_8") (pintype "passive"))
      (node (ref "R29") (pin "1") (pinfunction "1_1") (pintype "passive"))
    )
    (net (code "95") (name "Net-(JP4-Pad10)") (class "Default")
      (node (ref "JP4") (pin "10") (pinfunction "10_10") (pintype "passive"))
      (node (ref "R28") (pin "1") (pinfunction "1_1") (pintype "passive"))
    )
    (net (code "96") (name "Net-(JP4-Pad12)") (class "Default")
      (node (ref "JP4") (pin "12") (pinfunction "12_12") (pintype "passive"))
      (node (ref "R27") (pin "1") (pinfunction "1_1") (pintype "passive"))
    )
    (net (code "97") (name "Net-(JP4-Pad14)") (class "Default")
      (node (ref "JP4") (pin "14") (pinfunction "14_14") (pintype "passive"))
      (node (ref "R26") (pin "1") (pinfunction "1_1") (pintype "passive"))
    )
    (net (code "98") (name "Net-(JP4-Pad16)") (class "Default")
      (node (ref "JP4") (pin "16") (pinfunction "16_16") (pintype "passive"))
      (node (ref "R25") (pin "1") (pinfunction "1_1") (pintype "passive"))
    )
  )
)
